# main.net
KiCad netlist of a schematic drawn in EAGLE
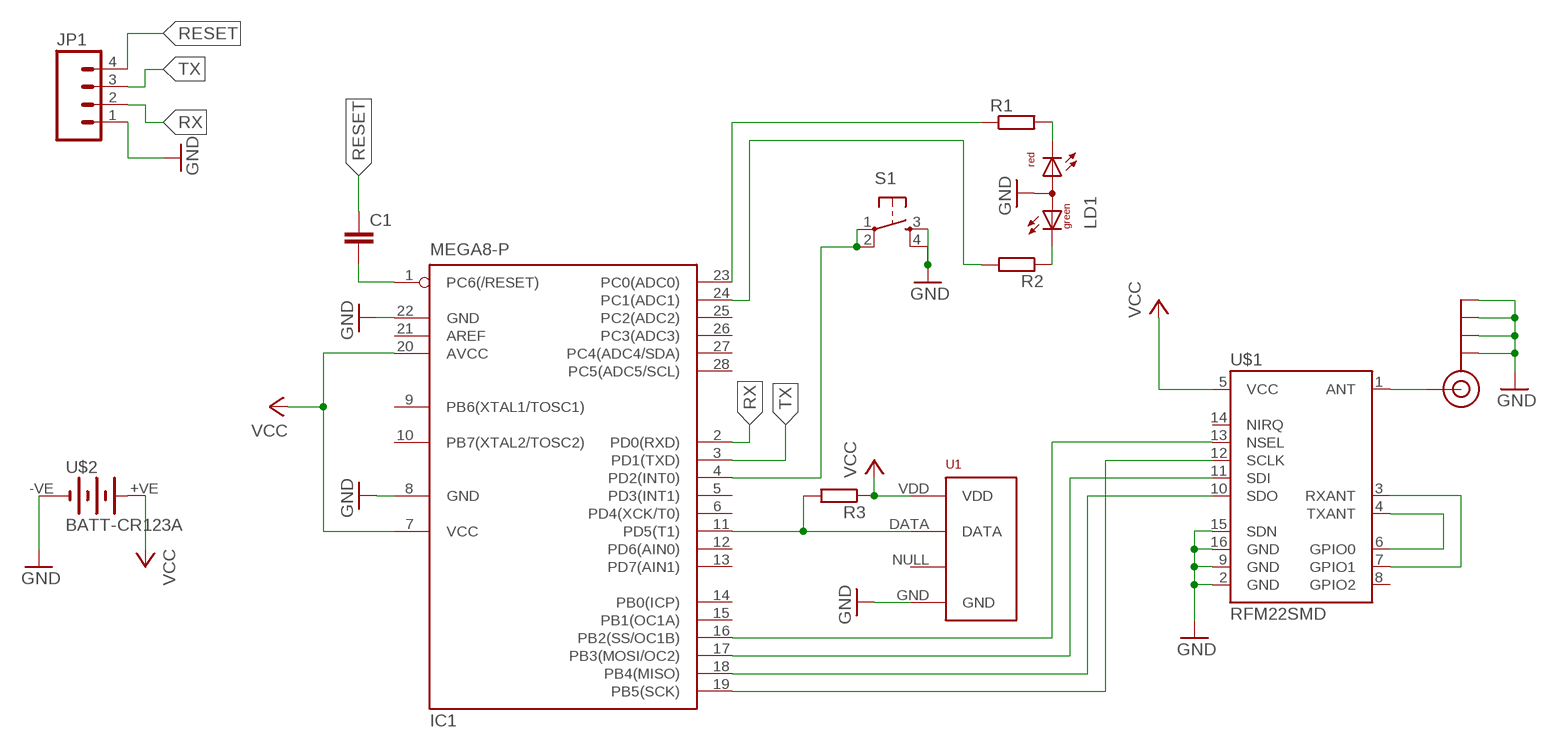
[diagram p0: schematic, sheet 1]

(export (version "E")
  (design (tool "Eeschema 10.0.6"))
  (components
    (comp (ref "C1")
      (value "C-EU050-025X075")
      (footprint "eagle-import:C050-025X075")
      (libsource (lib "eagle-import") (part "C-EU050-025X075"))
    )
    (comp (ref "IC1")
      (value "MEGA8-P")
      (footprint "eagle-import:DIL28-3")
      (libsource (lib "eagle-import") (part "MEGA8-P"))
    )
    (comp (ref "J$2")
      (value "SMA_EDGE")
      (footprint "eagle-import:SMA-EDGE")
      (libsource (lib "eagle-import") (part "SMA_EDGE"))
    )
    (comp (ref "JP1")
      (value "M04PTH")
      (footprint "eagle-import:1X04")
      (libsource (lib "eagle-import") (part "M04PTH"))
    )
    (comp (ref "LD1")
      (value "DUOLED-RG-A")
      (footprint "eagle-import:DUOLED-A-5MM")
      (libsource (lib "eagle-import") (part "DUOLED-RG-A"))
    )
    (comp (ref "R1")
      (value "R-EU_0204/5")
      (footprint "eagle-import:0204_5")
      (libsource (lib "eagle-import") (part "R-EU_0204/5"))
    )
    (comp (ref "R2")
      (value "R-EU_0204/5")
      (footprint "eagle-import:0204_5")
      (libsource (lib "eagle-import") (part "R-EU_0204/5"))
    )
    (comp (ref "R3")
      (value "R-EU_0204/5")
      (footprint "eagle-import:0204_5")
      (libsource (lib "eagle-import") (part "R-EU_0204/5"))
    )
    (comp (ref "S1")
      (value "TAC_SWITCHPTH")
      (footprint "eagle-import:TACTILE-PTH")
      (libsource (lib "eagle-import") (part "TAC_SWITCHPTH"))
    )
    (comp (ref "U$1")
      (value "RFM22SMD")
      (footprint "eagle-import:RFM22-XXX-S2")
      (libsource (lib "eagle-import") (part "RFM22SMD"))
    )
    (comp (ref "U$2")
      (value "BATT-CR123A")
      (footprint "eagle-import:KEYSTONE-2_3A")
      (libsource (lib "eagle-import") (part "BATT-CR123A"))
    )
    (comp (ref "U1")
      (value "RHT03_DHT-22_AM2302RA")
      (footprint "eagle-import:RHT03_DHT-22_RA")
      (libsource (lib "eagle-import") (part "RHT03_DHT-22_AM2302RA"))
    )
  )
  (nets
    (net (code "1") (name "GND") (class "Default")
      (node (ref "IC1") (pin "22") (pinfunction "GND_22") (pintype "power_in"))
      (node (ref "IC1") (pin "8") (pinfunction "GND_8") (pintype "power_in"))
      (node (ref "J$2") (pin "GND@0") (pinfunction "GND_GND@0") (pintype "bidirectional"))
      (node (ref "J$2") (pin "GND@1") (pinfunction "GND_GND@1") (pintype "bidirectional"))
      (node (ref "J$2") (pin "GND@2") (pinfunction "GND_GND@2") (pintype "bidirectional"))
      (node (ref "J$2") (pin "GND@3") (pinfunction "GND_GND@3") (pintype "bidirectional"))
      (node (ref "JP1") (pin "1") (pinfunction "1_1") (pintype "passive"))
      (node (ref "LD1") (pin "A") (pinfunction "A_A") (pintype "passive"))
      (node (ref "S1") (pin "3") (pinfunction "3_3") (pintype "passive"))
      (node (ref "S1") (pin "4") (pinfunction "4_4") (pintype "passive"))
      (node (ref "U$1") (pin "15") (pinfunction "SDN_15") (pintype "input"))
      (node (ref "U$1") (pin "16") (pinfunction "GND_16") (pintype "power_in"))
      (node (ref "U$1") (pin "2") (pinfunction "GND_2") (pintype "power_in"))
      (node (ref "U$1") (pin "9") (pinfunction "GND_9") (pintype "power_in"))
      (node (ref "U$2") (pin "-VE") (pinfunction "-_-VE") (pintype "passive"))
      (node (ref "U1") (pin "GND") (pinfunction "GND_GND") (pintype "power_in"))
    )
    (net (code "2") (name "Net-(IC1-PB2(SS{slash}OC1B))") (class "Default")
      (node (ref "IC1") (pin "16") (pinfunction "PB2(SS/OC1B)_16") (pintype "bidirectional"))
      (node (ref "U$1") (pin "13") (pinfunction "NSEL_13") (pintype "input"))
    )
    (net (code "3") (name "Net-(IC1-PB3(MOSI{slash}OC2))") (class "Default")
      (node (ref "IC1") (pin "17") (pinfunction "PB3(MOSI/OC2)_17") (pintype "bidirectional"))
      (node (ref "U$1") (pin "11") (pinfunction "SDI_11") (pintype "input"))
    )
    (net (code "4") (name "Net-(IC1-PB4(MISO))") (class "Default")
      (node (ref "IC1") (pin "18") (pinfunction "PB4(MISO)_18") (pintype "bidirectional"))
      (node (ref "U$1") (pin "10") (pinfunction "SDO_10") (pintype "output"))
    )
    (net (code "5") (name "Net-(IC1-PB5(SCK))") (class "Default")
      (node (ref "IC1") (pin "19") (pinfunction "PB5(SCK)_19") (pintype "bidirectional"))
      (node (ref "U$1") (pin "12") (pinfunction "SCLK_12") (pintype "input"))
    )
    (net (code "6") (name "Net-(IC1-PC0(ADC0))") (class "Default")
      (node (ref "IC1") (pin "23") (pinfunction "PC0(ADC0)_23") (pintype "bidirectional"))
      (node (ref "R1") (pin "1") (pinfunction "1_1") (pintype "passive"))
    )
    (net (code "7") (name "Net-(IC1-PC1(ADC1))") (class "Default")
      (node (ref "IC1") (pin "24") (pinfunction "PC1(ADC1)_24") (pintype "bidirectional"))
      (node (ref "R2") (pin "2") (pinfunction "2_2") (pintype "passive"))
    )
    (net (code "8") (name "Net-(IC1-PC6({slash}RESET))") (class "Default")
      (node (ref "C1") (pin "2") (pinfunction "2_2") (pintype "passive"))
      (node (ref "IC1") (pin "1") (pinfunction "PC6(/RESET)_1") (pintype "bidirectional"))
    )
    (net (code "9") (name "Net-(IC1-PD2(INT0))") (class "Default")
      (node (ref "IC1") (pin "4") (pinfunction "PD2(INT0)_4") (pintype "bidirectional"))
      (node (ref "S1") (pin "1") (pinfunction "1_1") (pintype "passive"))
      (node (ref "S1") (pin "2") (pinfunction "2_2") (pintype "passive"))
    )
    (net (code "10") (name "Net-(IC1-PD5(T1))") (class "Default")
      (node (ref "IC1") (pin "11") (pinfunction "PD5(T1)_11") (pintype "bidirectional"))
      (node (ref "R3") (pin "2") (pinfunction "2_2") (pintype "passive"))
      (node (ref "U1") (pin "DATA") (pinfunction "DATA_DATA") (pintype "bidirectional"))
    )
    (net (code "11") (name "Net-(J$2-SIGNAL)") (class "Default")
      (node (ref "J$2") (pin "SIG") (pinfunction "SIGNAL_SIG") (pintype "bidirectional"))
      (node (ref "U$1") (pin "1") (pinfunction "ANT_1") (pintype "bidirectional"))
    )
    (net (code "12") (name "Net-(LD1-CG)") (class "Default")
      (node (ref "LD1") (pin "CX") (pinfunction "CG_CX") (pintype "passive"))
      (node (ref "R2") (pin "1") (pinfunction "1_1") (pintype "passive"))
    )
    (net (code "13") (name "Net-(LD1-PadCR)") (class "Default")
      (node (ref "LD1") (pin "CR") (pinfunction "CR_CR") (pintype "passive"))
      (node (ref "R1") (pin "2") (pinfunction "2_2") (pintype "passive"))
    )
    (net (code "14") (name "Net-(U$1-GPIO0)") (class "Default")
      (node (ref "U$1") (pin "4") (pinfunction "TXANT_4") (pintype "input"))
      (node (ref "U$1") (pin "6") (pinfunction "GPIO0_6") (pintype "bidirectional"))
    )
    (net (code "15") (name "Net-(U$1-GPIO1)") (class "Default")
      (node (ref "U$1") (pin "3") (pinfunction "RXANT_3") (pintype "input"))
      (node (ref "U$1") (pin "7") (pinfunction "GPIO1_7") (pintype "bidirectional"))
    )
    (net (code "16") (name "RESET") (class "Default")
      (node (ref "C1") (pin "1") (pinfunction "1_1") (pintype "passive"))
      (node (ref "JP1") (pin "4") (pinfunction "4_4") (pintype "passive"))
    )
    (net (code "17") (name "RX") (class "Default")
      (node (ref "IC1") (pin "2") (pinfunction "PD0(RXD)_2") (pintype "bidirectional"))
      (node (ref "JP1") (pin "2") (pinfunction "2_2") (pintype "passive"))
    )
    (net (code "18") (name "TX") (class "Default")
      (node (ref "IC1") (pin "3") (pinfunction "PD1(TXD)_3") (pintype "bidirectional"))
      (node (ref "JP1") (pin "3") (pinfunction "3_3") (pintype "passive"))
    )
    (net (code "19") (name "VCC") (class "Default")
      (node (ref "IC1") (pin "20") (pinfunction "AVCC_20") (pintype "power_in"))
      (node (ref "IC1") (pin "7") (pinfunction "VCC_7") (pintype "power_in"))
      (node (ref "R3") (pin "1") (pinfunction "1_1") (pintype "passive"))
      (node (ref "U$1") (pin "5") (pinfunction "VCC_5") (pintype "bidirectional"))
      (node (ref "U$2") (pin "+VE") (pinfunction "+_+VE") (pintype "passive"))
      (node (ref "U1") (pin "VDD") (pinfunction "VDD_VDD") (pintype "power_in"))
    )
    (net (code "20") (name "unconnected-(IC1-AREF-Pad21)") (class "Default")
      (node (ref "IC1") (pin "21") (pinfunction "AREF_21") (pintype "passive"))
    )
    (net (code "21") (name "unconnected-(IC1-PB0(ICP)-Pad14)") (class "Default")
      (node (ref "IC1") (pin "14") (pinfunction "PB0(ICP)_14") (pintype "bidirectional"))
    )
    (net (code "22") (name "unconnected-(IC1-PB1(OC1A)-Pad15)") (class "Default")
      (node (ref "IC1") (pin "15") (pinfunction "PB1(OC1A)_15") (pintype "bidirectional"))
    )
    (net (code "23") (name "unconnected-(IC1-PB6(XTAL1{slash}TOSC1)-Pad9)") (class "Default")
      (node (ref "IC1") (pin "9") (pinfunction "PB6(XTAL1/TOSC1)_9") (pintype "bidirectional"))
    )
    (net (code "24") (name "unconnected-(IC1-PB7(XTAL2{slash}TOSC2)-Pad10)") (class "Default")
      (node (ref "IC1") (pin "10") (pinfunction "PB7(XTAL2/TOSC2)_10") (pintype "bidirectional"))
    )
    (net (code "25") (name "unconnected-(IC1-PC2(ADC2)-Pad25)") (class "Default")
      (node (ref "IC1") (pin "25") (pinfunction "PC2(ADC2)_25") (pintype "bidirectional"))
    )
    (net (code "26") (name "unconnected-(IC1-PC3(ADC3)-Pad26)") (class "Default")
      (node (ref "IC1") (pin "26") (pinfunction "PC3(ADC3)_26") (pintype "bidirectional"))
    )
    (net (code "27") (name "unconnected-(IC1-PC4(ADC4{slash}SDA)-Pad27)") (class "Default")
      (node (ref "IC1") (pin "27") (pinfunction "PC4(ADC4/SDA)_27") (pintype "bidirectional"))
    )
    (net (code "28") (name "unconnected-(IC1-PC5(ADC5{slash}SCL)-Pad28)") (class "Default")
      (node (ref "IC1") (pin "28") (pinfunction "PC5(ADC5/SCL)_28") (pintype "bidirectional"))
    )
    (net (code "29") (name "unconnected-(IC1-PD3(INT1)-Pad5)") (class "Default")
      (node (ref "IC1") (pin "5") (pinfunction "PD3(INT1)_5") (pintype "bidirectional"))
    )
    (net (code "30") (name "unconnected-(IC1-PD4(XCK{slash}T0)-Pad6)") (class "Default")
      (node (ref "IC1") (pin "6") (pinfunction "PD4(XCK/T0)_6") (pintype "bidirectional"))
    )
    (net (code "31") (name "unconnected-(IC1-PD6(AIN0)-Pad12)") (class "Default")
      (node (ref "IC1") (pin "12") (pinfunction "PD6(AIN0)_12") (pintype "bidirectional"))
    )
    (net (code "32") (name "unconnected-(IC1-PD7(AIN1)-Pad13)") (class "Default")
      (node (ref "IC1") (pin "13") (pinfunction "PD7(AIN1)_13") (pintype "bidirectional"))
    )
    (net (code "33") (name "unconnected-(U$1-GPIO2-Pad8)") (class "Default")
      (node (ref "U$1") (pin "8") (pinfunction "GPIO2_8") (pintype "bidirectional"))
    )
    (net (code "34") (name "unconnected-(U$1-NIRQ-Pad14)") (class "Default")
      (node (ref "U$1") (pin "14") (pinfunction "NIRQ_14") (pintype "output"))
    )
    (net (code "35") (name "unconnected-(U1-PadNULL)") (class "Default")
      (node (ref "U1") (pin "NULL") (pinfunction "NULL_NULL") (pintype "no_connect"))
    )
  )
)
